# FIT_HDMI_X32-26.net
KiCad netlist of a schematic drawn in Altium Designer
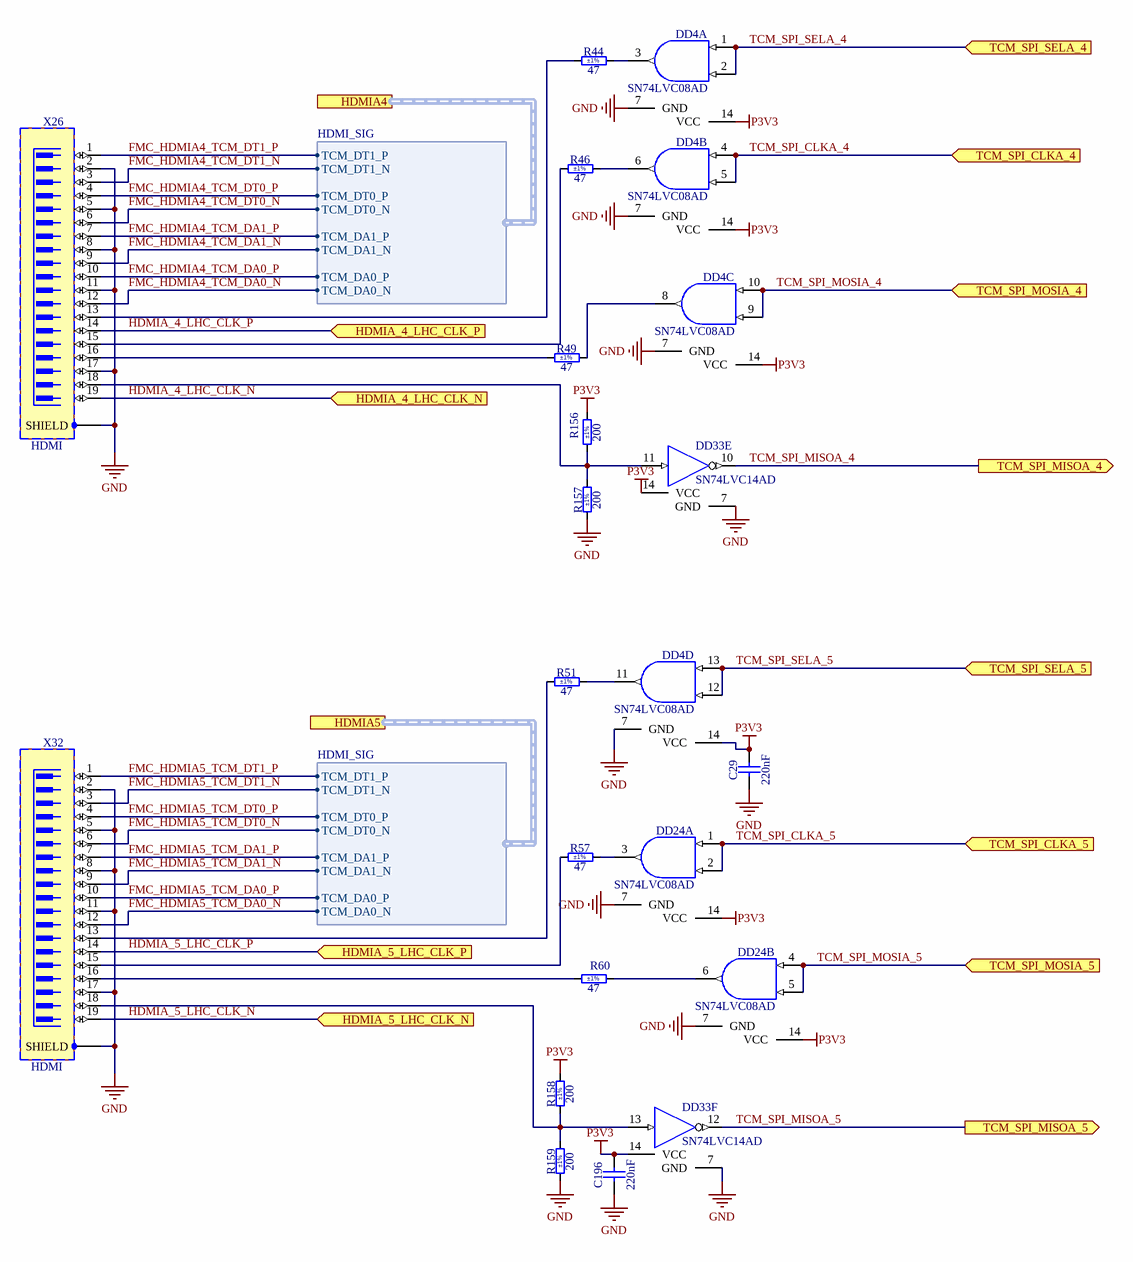
[diagram p0: FIT_HDMI_X32-26.SchDoc]

(export (version "E")
  (design (tool "Eeschema 10.0.6"))
  (components
    (comp (ref "C29")
      (value "220nF")
      (footprint "CAPC2012X135N")
      (description "Non-polarised capacitor")
      (fields
        (field (name "PART NUMBER") "CC0805_220NF_50V_10%_X7R")
        (field (name "VOLTAGE") "50V")
        (field (name "AUTHOR") "CERN DEM JLC")
      )
      (libsource (lib "Capacitors") (part "Capacitor - non polarized"))
    )
    (comp (ref "C196")
      (value "220nF")
      (footprint "CAPC2012X135N")
      (description "Non-polarised capacitor")
      (fields
        (field (name "PART NUMBER") "CC0805_220NF_50V_10%_X7R")
        (field (name "VOLTAGE") "50V")
        (field (name "AUTHOR") "CERN DEM JLC")
      )
      (libsource (lib "Capacitors") (part "Capacitor - non polarized"))
    )
    (comp (ref "DD4")
      (value "SN74LVC08AD")
      (footprint "SOIC127P600X175-14N")
      (description "Quad 2-Input AND Gate")
      (fields (field (name "MANUFACTURER") "TEXAS INSTRUMENTS") (field (name "AUTHOR") "CERN DEM JLC"))
      (libsource (lib "ICs And Semiconductors") (part "7408"))
    )
    (comp (ref "DD24")
      (value "SN74LVC08AD")
      (footprint "SOIC127P600X175-14N")
      (description "Quad 2-Input AND Gate")
      (fields (field (name "MANUFACTURER") "TEXAS INSTRUMENTS") (field (name "AUTHOR") "CERN DEM JLC"))
      (libsource (lib "ICs And Semiconductors") (part "7408"))
    )
    (comp (ref "DD33")
      (value "SN74LVC14AD")
      (footprint "SOIC127P600X175-14N")
      (description "Hex Schmitt-Trigger Inverter")
      (fields (field (name "MANUFACTURER") "TEXAS INSTRUMENTS") (field (name "AUTHOR") "CERN DEM JMW"))
      (libsource (lib "ICs And Semiconductors") (part "7414"))
    )
    (comp (ref "R44")
      (value "47")
      (footprint "RESC2012X60N")
      (description "Resistor - 1%")
      (fields
        (field (name "TOLERANCE") "±1%")
        (field (name "PART NUMBER") "R0805_47R_1%_0.125W_100PPM")
        (field (name "POWER") "0.125W")
        (field (name "AUTHOR") "CERN DEM JLC")
      )
      (libsource (lib "Resistors") (part "Resistor - 1%"))
    )
    (comp (ref "R46")
      (value "47")
      (footprint "RESC2012X60N")
      (description "Resistor - 1%")
      (fields
        (field (name "TOLERANCE") "±1%")
        (field (name "PART NUMBER") "R0805_47R_1%_0.125W_100PPM")
        (field (name "POWER") "0.125W")
        (field (name "AUTHOR") "CERN DEM JLC")
      )
      (libsource (lib "Resistors") (part "Resistor - 1%"))
    )
    (comp (ref "R49")
      (value "47")
      (footprint "RESC2012X60N")
      (description "Resistor - 1%")
      (fields
        (field (name "TOLERANCE") "±1%")
        (field (name "PART NUMBER") "R0805_47R_1%_0.125W_100PPM")
        (field (name "POWER") "0.125W")
        (field (name "AUTHOR") "CERN DEM JLC")
      )
      (libsource (lib "Resistors") (part "Resistor - 1%"))
    )
    (comp (ref "R51")
      (value "47")
      (footprint "RESC2012X60N")
      (description "Resistor - 1%")
      (fields
        (field (name "TOLERANCE") "±1%")
        (field (name "PART NUMBER") "R0805_47R_1%_0.125W_100PPM")
        (field (name "POWER") "0.125W")
        (field (name "AUTHOR") "CERN DEM JLC")
      )
      (libsource (lib "Resistors") (part "Resistor - 1%"))
    )
    (comp (ref "R57")
      (value "47")
      (footprint "RESC2012X60N")
      (description "Resistor - 1%")
      (fields
        (field (name "TOLERANCE") "±1%")
        (field (name "PART NUMBER") "R0805_47R_1%_0.125W_100PPM")
        (field (name "POWER") "0.125W")
        (field (name "AUTHOR") "CERN DEM JLC")
      )
      (libsource (lib "Resistors") (part "Resistor - 1%"))
    )
    (comp (ref "R60")
      (value "47")
      (footprint "RESC2012X60N")
      (description "Resistor - 1%")
      (fields
        (field (name "TOLERANCE") "±1%")
        (field (name "PART NUMBER") "R0805_47R_1%_0.125W_100PPM")
        (field (name "POWER") "0.125W")
        (field (name "AUTHOR") "CERN DEM JLC")
      )
      (libsource (lib "Resistors") (part "Resistor - 1%"))
    )
    (comp (ref "R156")
      (value "200")
      (footprint "RESC2012X60N")
      (description "Resistor - 1%")
      (fields
        (field (name "TOLERANCE") "±1%")
        (field (name "PART NUMBER") "R0805_200R_1%_0.125W_100PPM")
        (field (name "POWER") "0.125W")
        (field (name "AUTHOR") "CERN DEM JLC")
      )
      (libsource (lib "Resistors") (part "Resistor - 1%"))
    )
    (comp (ref "R157")
      (value "200")
      (footprint "RESC2012X60N")
      (description "Resistor - 1%")
      (fields
        (field (name "TOLERANCE") "±1%")
        (field (name "PART NUMBER") "R0805_200R_1%_0.125W_100PPM")
        (field (name "POWER") "0.125W")
        (field (name "AUTHOR") "CERN DEM JLC")
      )
      (libsource (lib "Resistors") (part "Resistor - 1%"))
    )
    (comp (ref "R158")
      (value "200")
      (footprint "RESC2012X60N")
      (description "Resistor - 1%")
      (fields
        (field (name "TOLERANCE") "±1%")
        (field (name "PART NUMBER") "R0805_200R_1%_0.125W_100PPM")
        (field (name "POWER") "0.125W")
        (field (name "AUTHOR") "CERN DEM JLC")
      )
      (libsource (lib "Resistors") (part "Resistor - 1%"))
    )
    (comp (ref "R159")
      (value "200")
      (footprint "RESC2012X60N")
      (description "Resistor - 1%")
      (fields
        (field (name "TOLERANCE") "±1%")
        (field (name "PART NUMBER") "R0805_200R_1%_0.125W_100PPM")
        (field (name "POWER") "0.125W")
        (field (name "AUTHOR") "CERN DEM JLC")
      )
      (libsource (lib "Resistors") (part "Resistor - 1%"))
    )
    (comp (ref "X26")
      (value "HDMI")
      (footprint "TYCO_2007435-1")
      (description "Connector HDMI 19 Male + 1 Shield")
      (fields
        (field (name "PART NUMBER") "TYCO_2007435-1")
        (field (name "MANUFACTURER") "TYCO ELECTRONICS")
        (field (name "AUTHOR") "CERN DEM MR")
      )
      (libsource (lib "Connectors") (part "Connector HDMI 19 Male + 1 Shield"))
    )
    (comp (ref "X32")
      (value "HDMI")
      (footprint "TYCO_2007435-1")
      (description "Connector HDMI 19 Male + 1 Shield")
      (fields
        (field (name "PART NUMBER") "TYCO_2007435-1")
        (field (name "MANUFACTURER") "TYCO ELECTRONICS")
        (field (name "AUTHOR") "CERN DEM MR")
      )
      (libsource (lib "Connectors") (part "Connector HDMI 19 Male + 1 Shield"))
    )
  )
  (nets
    (net (code "2") (name "/FMC_HDMIA4_TCM_DA0_N") (class "Default")
      (node (ref "X26") (pin "12") (pinfunction "12_12") (pintype "bidirectional"))
    )
    (net (code "3") (name "/FMC_HDMIA4_TCM_DA0_P") (class "Default")
      (node (ref "X26") (pin "10") (pinfunction "10_10") (pintype "bidirectional"))
    )
    (net (code "4") (name "/FMC_HDMIA4_TCM_DA1_N") (class "Default")
      (node (ref "X26") (pin "9") (pinfunction "9_9") (pintype "bidirectional"))
    )
    (net (code "5") (name "/FMC_HDMIA4_TCM_DA1_P") (class "Default")
      (node (ref "X26") (pin "7") (pinfunction "7_7") (pintype "bidirectional"))
    )
    (net (code "6") (name "/FMC_HDMIA4_TCM_DT0_N") (class "Default")
      (node (ref "X26") (pin "6") (pinfunction "6_6") (pintype "bidirectional"))
    )
    (net (code "7") (name "/FMC_HDMIA4_TCM_DT0_P") (class "Default")
      (node (ref "X26") (pin "4") (pinfunction "4_4") (pintype "bidirectional"))
    )
    (net (code "8") (name "/FMC_HDMIA4_TCM_DT1_N") (class "Default")
      (node (ref "X26") (pin "3") (pinfunction "3_3") (pintype "bidirectional"))
    )
    (net (code "9") (name "/FMC_HDMIA4_TCM_DT1_P") (class "Default")
      (node (ref "X26") (pin "1") (pinfunction "1_1") (pintype "bidirectional"))
    )
    (net (code "10") (name "/FMC_HDMIA5_TCM_DA0_N") (class "Default")
      (node (ref "X32") (pin "12") (pinfunction "12_12") (pintype "bidirectional"))
    )
    (net (code "11") (name "/FMC_HDMIA5_TCM_DA0_P") (class "Default")
      (node (ref "X32") (pin "10") (pinfunction "10_10") (pintype "bidirectional"))
    )
    (net (code "12") (name "/FMC_HDMIA5_TCM_DA1_N") (class "Default")
      (node (ref "X32") (pin "9") (pinfunction "9_9") (pintype "bidirectional"))
    )
    (net (code "13") (name "/FMC_HDMIA5_TCM_DA1_P") (class "Default")
      (node (ref "X32") (pin "7") (pinfunction "7_7") (pintype "bidirectional"))
    )
    (net (code "14") (name "/FMC_HDMIA5_TCM_DT0_N") (class "Default")
      (node (ref "X32") (pin "6") (pinfunction "6_6") (pintype "bidirectional"))
    )
    (net (code "15") (name "/FMC_HDMIA5_TCM_DT0_P") (class "Default")
      (node (ref "X32") (pin "4") (pinfunction "4_4") (pintype "bidirectional"))
    )
    (net (code "16") (name "/FMC_HDMIA5_TCM_DT1_N") (class "Default")
      (node (ref "X32") (pin "3") (pinfunction "3_3") (pintype "bidirectional"))
    )
    (net (code "17") (name "/FMC_HDMIA5_TCM_DT1_P") (class "Default")
      (node (ref "X32") (pin "1") (pinfunction "1_1") (pintype "bidirectional"))
    )
    (net (code "18") (name "/HDMIA_4_LHC_CLK_N") (class "Default")
      (node (ref "X26") (pin "19") (pinfunction "19_19") (pintype "bidirectional"))
    )
    (net (code "19") (name "/HDMIA_4_LHC_CLK_P") (class "Default")
      (node (ref "X26") (pin "14") (pinfunction "14_14") (pintype "bidirectional"))
    )
    (net (code "20") (name "/HDMIA_5_LHC_CLK_N") (class "Default")
      (node (ref "X32") (pin "19") (pinfunction "19_19") (pintype "bidirectional"))
    )
    (net (code "21") (name "/HDMIA_5_LHC_CLK_P") (class "Default")
      (node (ref "X32") (pin "14") (pinfunction "14_14") (pintype "bidirectional"))
    )
    (net (code "22") (name "/TCM_SPI_CLKA_4") (class "Default")
      (node (ref "DD4") (pin "4") (pinfunction "A_4") (pintype "input"))
      (node (ref "DD4") (pin "5") (pinfunction "B_5") (pintype "input"))
    )
    (net (code "23") (name "/TCM_SPI_CLKA_5") (class "Default")
      (node (ref "DD24") (pin "1") (pinfunction "A_1") (pintype "input"))
      (node (ref "DD24") (pin "2") (pinfunction "B_2") (pintype "input"))
    )
    (net (code "24") (name "/TCM_SPI_MISOA_4") (class "Default")
      (node (ref "DD33") (pin "10") (pinfunction "OUT_10") (pintype "output"))
    )
    (net (code "25") (name "/TCM_SPI_MISOA_5") (class "Default")
      (node (ref "DD33") (pin "12") (pinfunction "OUT_12") (pintype "output"))
    )
    (net (code "26") (name "/TCM_SPI_MOSIA_4") (class "Default")
      (node (ref "DD4") (pin "10") (pinfunction "A_10") (pintype "input"))
      (node (ref "DD4") (pin "9") (pinfunction "B_9") (pintype "input"))
    )
    (net (code "27") (name "/TCM_SPI_MOSIA_5") (class "Default")
      (node (ref "DD24") (pin "4") (pinfunction "A_4") (pintype "input"))
      (node (ref "DD24") (pin "5") (pinfunction "B_5") (pintype "input"))
    )
    (net (code "28") (name "/TCM_SPI_SELA_4") (class "Default")
      (node (ref "DD4") (pin "1") (pinfunction "A_1") (pintype "input"))
      (node (ref "DD4") (pin "2") (pinfunction "B_2") (pintype "input"))
    )
    (net (code "29") (name "/TCM_SPI_SELA_5") (class "Default")
      (node (ref "DD4") (pin "12") (pinfunction "B_12") (pintype "input"))
      (node (ref "DD4") (pin "13") (pinfunction "A_13") (pintype "input"))
    )
    (net (code "31") (name "GND") (class "Default")
      (node (ref "C196") (pin "1") (pinfunction "1_1") (pintype "passive"))
      (node (ref "C29") (pin "1") (pinfunction "1_1") (pintype "passive"))
      (node (ref "DD24") (pin "7") (pinfunction "GND_7") (pintype "power_in"))
      (node (ref "DD33") (pin "7") (pinfunction "GND_7") (pintype "power_in"))
      (node (ref "DD4") (pin "7") (pinfunction "GND_7") (pintype "power_in"))
      (node (ref "R157") (pin "1") (pinfunction "1_1") (pintype "passive"))
      (node (ref "R159") (pin "1") (pinfunction "1_1") (pintype "passive"))
      (node (ref "X26") (pin "11") (pinfunction "11_11") (pintype "bidirectional"))
      (node (ref "X26") (pin "17") (pinfunction "17_17") (pintype "bidirectional"))
      (node (ref "X26") (pin "2") (pinfunction "2_2") (pintype "bidirectional"))
      (node (ref "X26") (pin "5") (pinfunction "5_5") (pintype "bidirectional"))
      (node (ref "X26") (pin "8") (pinfunction "8_8") (pintype "bidirectional"))
      (node (ref "X26") (pin "SHIELD") (pinfunction "SHIELD_SHIELD") (pintype "power_in"))
      (node (ref "X32") (pin "11") (pinfunction "11_11") (pintype "bidirectional"))
      (node (ref "X32") (pin "17") (pinfunction "17_17") (pintype "bidirectional"))
      (node (ref "X32") (pin "2") (pinfunction "2_2") (pintype "bidirectional"))
      (node (ref "X32") (pin "5") (pinfunction "5_5") (pintype "bidirectional"))
      (node (ref "X32") (pin "8") (pinfunction "8_8") (pintype "bidirectional"))
      (node (ref "X32") (pin "SHIELD") (pinfunction "SHIELD_SHIELD") (pintype "power_in"))
    )
    (net (code "32") (name "Net-(DD4A-Y)") (class "Default")
      (node (ref "DD4") (pin "3") (pinfunction "Y_3") (pintype "output"))
      (node (ref "R44") (pin "2") (pinfunction "2_2") (pintype "passive"))
    )
    (net (code "33") (name "Net-(DD4B-Y)") (class "Default")
      (node (ref "DD4") (pin "6") (pinfunction "Y_6") (pintype "output"))
      (node (ref "R46") (pin "2") (pinfunction "2_2") (pintype "passive"))
    )
    (net (code "34") (name "Net-(DD4C-Y)") (class "Default")
      (node (ref "DD4") (pin "8") (pinfunction "Y_8") (pintype "output"))
      (node (ref "R49") (pin "2") (pinfunction "2_2") (pintype "passive"))
    )
    (net (code "35") (name "Net-(DD4D-Y)") (class "Default")
      (node (ref "DD4") (pin "11") (pinfunction "Y_11") (pintype "output"))
      (node (ref "R51") (pin "2") (pinfunction "2_2") (pintype "passive"))
    )
    (net (code "36") (name "Net-(DD24A-Y)") (class "Default")
      (node (ref "DD24") (pin "3") (pinfunction "Y_3") (pintype "output"))
      (node (ref "R57") (pin "2") (pinfunction "2_2") (pintype "passive"))
    )
    (net (code "37") (name "Net-(DD24B-Y)") (class "Default")
      (node (ref "DD24") (pin "6") (pinfunction "Y_6") (pintype "output"))
      (node (ref "R60") (pin "2") (pinfunction "2_2") (pintype "passive"))
    )
    (net (code "38") (name "Net-(DD33E-IN)") (class "Default")
      (node (ref "DD33") (pin "11") (pinfunction "IN_11") (pintype "input"))
      (node (ref "R156") (pin "1") (pinfunction "1_1") (pintype "passive"))
      (node (ref "R157") (pin "2") (pinfunction "2_2") (pintype "passive"))
      (node (ref "X26") (pin "18") (pinfunction "18_18") (pintype "bidirectional"))
    )
    (net (code "39") (name "Net-(DD33F-IN)") (class "Default")
      (node (ref "DD33") (pin "13") (pinfunction "IN_13") (pintype "input"))
      (node (ref "R158") (pin "1") (pinfunction "1_1") (pintype "passive"))
      (node (ref "R159") (pin "2") (pinfunction "2_2") (pintype "passive"))
      (node (ref "X32") (pin "18") (pinfunction "18_18") (pintype "bidirectional"))
    )
    (net (code "40") (name "Net-(R44-Pad1)") (class "Default")
      (node (ref "R44") (pin "1") (pinfunction "1_1") (pintype "passive"))
      (node (ref "X26") (pin "13") (pinfunction "13_13") (pintype "bidirectional"))
    )
    (net (code "41") (name "Net-(R46-Pad1)") (class "Default")
      (node (ref "R46") (pin "1") (pinfunction "1_1") (pintype "passive"))
      (node (ref "X26") (pin "15") (pinfunction "15_15") (pintype "bidirectional"))
    )
    (net (code "42") (name "Net-(R49-Pad1)") (class "Default")
      (node (ref "R49") (pin "1") (pinfunction "1_1") (pintype "passive"))
      (node (ref "X26") (pin "16") (pinfunction "16_16") (pintype "bidirectional"))
    )
    (net (code "43") (name "Net-(R51-Pad1)") (class "Default")
      (node (ref "R51") (pin "1") (pinfunction "1_1") (pintype "passive"))
      (node (ref "X32") (pin "13") (pinfunction "13_13") (pintype "bidirectional"))
    )
    (net (code "44") (name "Net-(R57-Pad1)") (class "Default")
      (node (ref "R57") (pin "1") (pinfunction "1_1") (pintype "passive"))
      (node (ref "X32") (pin "15") (pinfunction "15_15") (pintype "bidirectional"))
    )
    (net (code "45") (name "Net-(R60-Pad1)") (class "Default")
      (node (ref "R60") (pin "1") (pinfunction "1_1") (pintype "passive"))
      (node (ref "X32") (pin "16") (pinfunction "16_16") (pintype "bidirectional"))
    )
    (net (code "46") (name "P3V3") (class "Default")
      (node (ref "C196") (pin "2") (pinfunction "2_2") (pintype "passive"))
      (node (ref "C29") (pin "2") (pinfunction "2_2") (pintype "passive"))
      (node (ref "DD24") (pin "14") (pinfunction "VCC_14") (pintype "power_in"))
      (node (ref "DD33") (pin "14") (pinfunction "VCC_14") (pintype "power_in"))
      (node (ref "DD4") (pin "14") (pinfunction "VCC_14") (pintype "power_in"))
      (node (ref "R156") (pin "2") (pinfunction "2_2") (pintype "passive"))
      (node (ref "R158") (pin "2") (pinfunction "2_2") (pintype "passive"))
    )
  )
)
